# Clock_fanout.net
KiCad netlist of a schematic drawn in Altium Designer
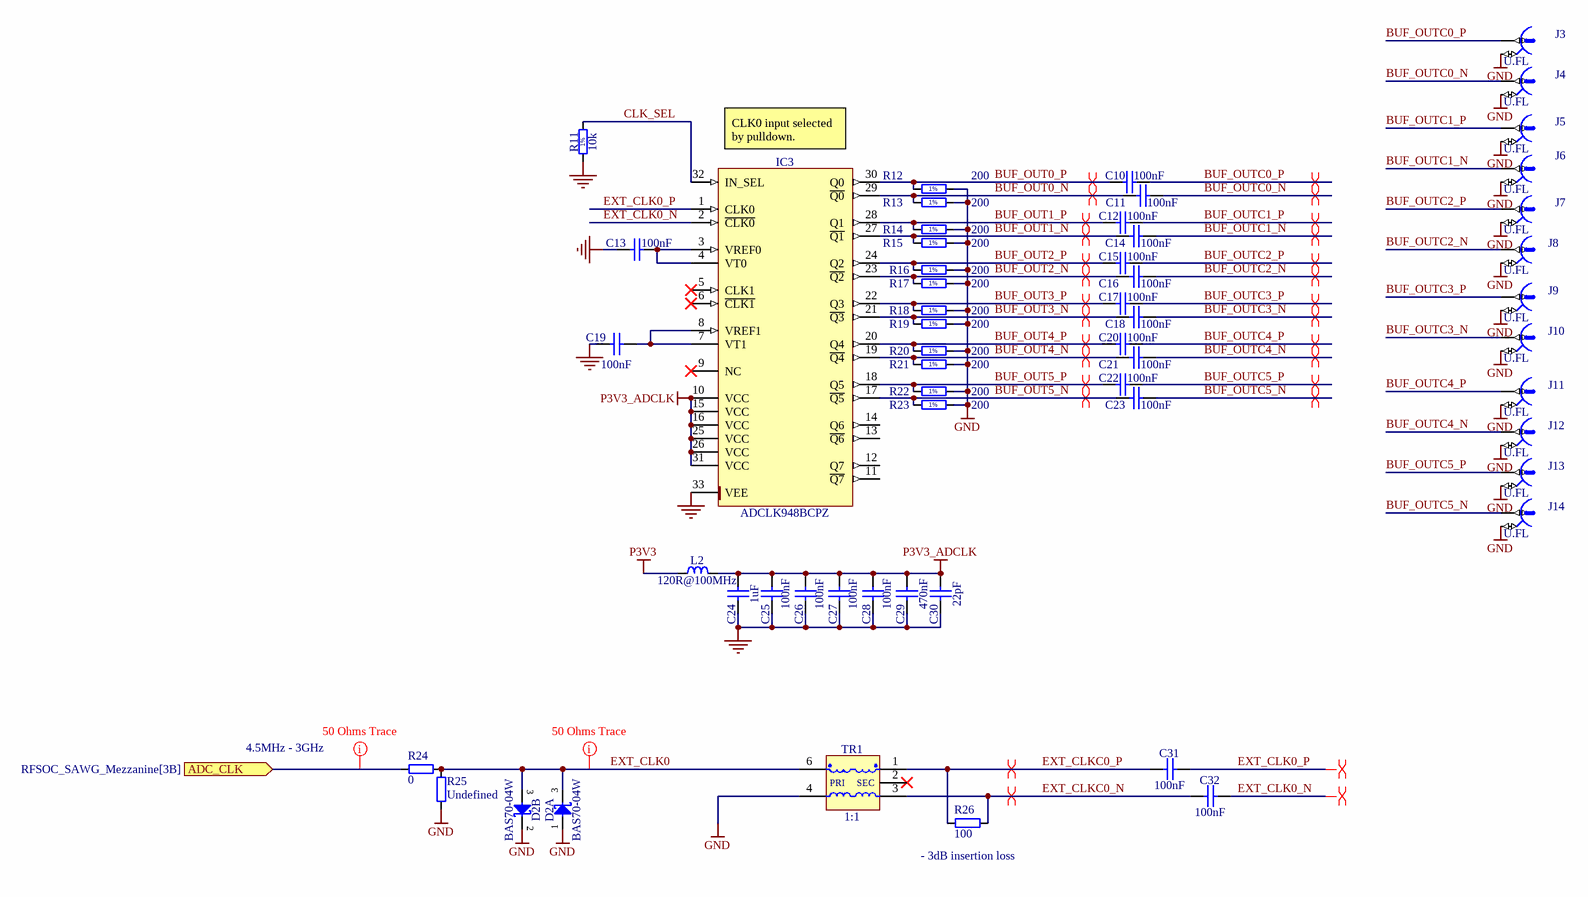
[diagram p0: Clock_fanout.SchDoc]

(export (version "E")
  (design (tool "Eeschema 10.0.6"))
  (components
    (comp (ref "C10")
      (value "100nF")
      (footprint "CAPC0603X33N")
      (description "Non-polarised capacitor")
      (fields
        (field (name "PART NUMBER") "CC0201_100NF_6.3V_10%_X5R")
        (field (name "VOLTAGE") "6.3V")
        (field (name "AUTHOR") "CERN DEM JLC")
      )
      (libsource (lib "Capacitors") (part "Capacitor - non polarized"))
    )
    (comp (ref "C11")
      (value "100nF")
      (footprint "CAPC0603X33N")
      (description "Non-polarised capacitor")
      (fields
        (field (name "PART NUMBER") "CC0201_100NF_6.3V_10%_X5R")
        (field (name "VOLTAGE") "6.3V")
        (field (name "AUTHOR") "CERN DEM JLC")
      )
      (libsource (lib "Capacitors") (part "Capacitor - non polarized"))
    )
    (comp (ref "C12")
      (value "100nF")
      (footprint "CAPC0603X33N")
      (description "Non-polarised capacitor")
      (fields
        (field (name "PART NUMBER") "CC0201_100NF_6.3V_10%_X5R")
        (field (name "VOLTAGE") "6.3V")
        (field (name "AUTHOR") "CERN DEM JLC")
      )
      (libsource (lib "Capacitors") (part "Capacitor - non polarized"))
    )
    (comp (ref "C13")
      (value "100nF")
      (footprint "CAPC0603X33N")
      (description "Non-polarised capacitor")
      (fields
        (field (name "PART NUMBER") "CC0201_100NF_6.3V_10%_X5R")
        (field (name "VOLTAGE") "6.3V")
        (field (name "AUTHOR") "CERN DEM JLC")
      )
      (libsource (lib "Capacitors") (part "Capacitor - non polarized"))
    )
    (comp (ref "C14")
      (value "100nF")
      (footprint "CAPC0603X33N")
      (description "Non-polarised capacitor")
      (fields
        (field (name "PART NUMBER") "CC0201_100NF_6.3V_10%_X5R")
        (field (name "VOLTAGE") "6.3V")
        (field (name "AUTHOR") "CERN DEM JLC")
      )
      (libsource (lib "Capacitors") (part "Capacitor - non polarized"))
    )
    (comp (ref "C15")
      (value "100nF")
      (footprint "CAPC0603X33N")
      (description "Non-polarised capacitor")
      (fields
        (field (name "PART NUMBER") "CC0201_100NF_6.3V_10%_X5R")
        (field (name "VOLTAGE") "6.3V")
        (field (name "AUTHOR") "CERN DEM JLC")
      )
      (libsource (lib "Capacitors") (part "Capacitor - non polarized"))
    )
    (comp (ref "C16")
      (value "100nF")
      (footprint "CAPC0603X33N")
      (description "Non-polarised capacitor")
      (fields
        (field (name "PART NUMBER") "CC0201_100NF_6.3V_10%_X5R")
        (field (name "VOLTAGE") "6.3V")
        (field (name "AUTHOR") "CERN DEM JLC")
      )
      (libsource (lib "Capacitors") (part "Capacitor - non polarized"))
    )
    (comp (ref "C17")
      (value "100nF")
      (footprint "CAPC0603X33N")
      (description "Non-polarised capacitor")
      (fields
        (field (name "PART NUMBER") "CC0201_100NF_6.3V_10%_X5R")
        (field (name "VOLTAGE") "6.3V")
        (field (name "AUTHOR") "CERN DEM JLC")
      )
      (libsource (lib "Capacitors") (part "Capacitor - non polarized"))
    )
    (comp (ref "C18")
      (value "100nF")
      (footprint "CAPC0603X33N")
      (description "Non-polarised capacitor")
      (fields
        (field (name "PART NUMBER") "CC0201_100NF_6.3V_10%_X5R")
        (field (name "VOLTAGE") "6.3V")
        (field (name "AUTHOR") "CERN DEM JLC")
      )
      (libsource (lib "Capacitors") (part "Capacitor - non polarized"))
    )
    (comp (ref "C19")
      (value "100nF")
      (footprint "CAPC0603X33N")
      (description "Non-polarised capacitor")
      (fields
        (field (name "PART NUMBER") "CC0201_100NF_6.3V_10%_X5R")
        (field (name "VOLTAGE") "6.3V")
        (field (name "AUTHOR") "CERN DEM JLC")
      )
      (libsource (lib "Capacitors") (part "Capacitor - non polarized"))
    )
    (comp (ref "C20")
      (value "100nF")
      (footprint "CAPC0603X33N")
      (description "Non-polarised capacitor")
      (fields
        (field (name "PART NUMBER") "CC0201_100NF_6.3V_10%_X5R")
        (field (name "VOLTAGE") "6.3V")
        (field (name "AUTHOR") "CERN DEM JLC")
      )
      (libsource (lib "Capacitors") (part "Capacitor - non polarized"))
    )
    (comp (ref "C21")
      (value "100nF")
      (footprint "CAPC0603X33N")
      (description "Non-polarised capacitor")
      (fields
        (field (name "PART NUMBER") "CC0201_100NF_6.3V_10%_X5R")
        (field (name "VOLTAGE") "6.3V")
        (field (name "AUTHOR") "CERN DEM JLC")
      )
      (libsource (lib "Capacitors") (part "Capacitor - non polarized"))
    )
    (comp (ref "C22")
      (value "100nF")
      (footprint "CAPC0603X33N")
      (description "Non-polarised capacitor")
      (fields
        (field (name "PART NUMBER") "CC0201_100NF_6.3V_10%_X5R")
        (field (name "VOLTAGE") "6.3V")
        (field (name "AUTHOR") "CERN DEM JLC")
      )
      (libsource (lib "Capacitors") (part "Capacitor - non polarized"))
    )
    (comp (ref "C23")
      (value "100nF")
      (footprint "CAPC0603X33N")
      (description "Non-polarised capacitor")
      (fields
        (field (name "PART NUMBER") "CC0201_100NF_6.3V_10%_X5R")
        (field (name "VOLTAGE") "6.3V")
        (field (name "AUTHOR") "CERN DEM JLC")
      )
      (libsource (lib "Capacitors") (part "Capacitor - non polarized"))
    )
    (comp (ref "C24")
      (value "1uF")
      (footprint "CAPC1005X55N")
      (description "Non-polarised capacitor")
      (fields
        (field (name "PART NUMBER") "CC0402_1UF_16V_10%_X5R")
        (field (name "VOLTAGE") "16V")
        (field (name "AUTHOR") "CERN DEM JLC")
      )
      (libsource (lib "Capacitors") (part "Capacitor - non polarized"))
    )
    (comp (ref "C25")
      (value "100nF")
      (footprint "CAPC0603X33N")
      (description "Non-polarised capacitor")
      (fields
        (field (name "PART NUMBER") "CC0201_100NF_6.3V_10%_X5R")
        (field (name "VOLTAGE") "6.3V")
        (field (name "AUTHOR") "CERN DEM JLC")
      )
      (libsource (lib "Capacitors") (part "Capacitor - non polarized"))
    )
    (comp (ref "C26")
      (value "100nF")
      (footprint "CAPC0603X33N")
      (description "Non-polarised capacitor")
      (fields
        (field (name "PART NUMBER") "CC0201_100NF_6.3V_10%_X5R")
        (field (name "VOLTAGE") "6.3V")
        (field (name "AUTHOR") "CERN DEM JLC")
      )
      (libsource (lib "Capacitors") (part "Capacitor - non polarized"))
    )
    (comp (ref "C27")
      (value "100nF")
      (footprint "CAPC0603X33N")
      (description "Non-polarised capacitor")
      (fields
        (field (name "PART NUMBER") "CC0201_100NF_6.3V_10%_X5R")
        (field (name "VOLTAGE") "6.3V")
        (field (name "AUTHOR") "CERN DEM JLC")
      )
      (libsource (lib "Capacitors") (part "Capacitor - non polarized"))
    )
    (comp (ref "C28")
      (value "100nF")
      (footprint "CAPC0603X33N")
      (description "Non-polarised capacitor")
      (fields
        (field (name "PART NUMBER") "CC0201_100NF_6.3V_10%_X5R")
        (field (name "VOLTAGE") "6.3V")
        (field (name "AUTHOR") "CERN DEM JLC")
      )
      (libsource (lib "Capacitors") (part "Capacitor - non polarized"))
    )
    (comp (ref "C29")
      (value "470nF")
      (footprint "CAPC0603X33N")
      (description "Non-polarised capacitor")
      (fields
        (field (name "PART NUMBER") "CC0201_470NF_4V_20%_X5R")
        (field (name "VOLTAGE") "4V")
        (field (name "AUTHOR") "CERN DEM JLC")
      )
      (libsource (lib "Capacitors") (part "Capacitor - non polarized"))
    )
    (comp (ref "C30")
      (value "22pF")
      (footprint "CAPC1005X55N")
      (description "Non-polarised capacitor")
      (fields
        (field (name "PART NUMBER") "CC0402_22PF_50V_5%_C0G")
        (field (name "VOLTAGE") "50V")
        (field (name "AUTHOR") "CERN DEM JLC")
      )
      (libsource (lib "Capacitors") (part "Capacitor - non polarized"))
    )
    (comp (ref "C31")
      (value "100nF")
      (footprint "CAPC0603X33N")
      (description "Non-polarised capacitor")
      (fields
        (field (name "PART NUMBER") "CC0201_100NF_6.3V_10%_X5R")
        (field (name "VOLTAGE") "6.3V")
        (field (name "AUTHOR") "CERN DEM JLC")
      )
      (libsource (lib "Capacitors") (part "Capacitor - non polarized"))
    )
    (comp (ref "C32")
      (value "100nF")
      (footprint "CAPC0603X33N")
      (description "Non-polarised capacitor")
      (fields
        (field (name "PART NUMBER") "CC0201_100NF_6.3V_10%_X5R")
        (field (name "VOLTAGE") "6.3V")
        (field (name "AUTHOR") "CERN DEM JLC")
      )
      (libsource (lib "Capacitors") (part "Capacitor - non polarized"))
    )
    (comp (ref "D2")
      (value "BAS70-04W")
      (footprint "SOT65P210X110-3N")
      (description "Serial Schottky Diode")
      (fields
        (field (name "VOLTAGE") "70V")
        (field (name "POWER") "70mA")
        (field (name "AUTHOR") "CERN DEM JLC")
      )
      (libsource (lib "ICs And Semiconductors") (part "Diode Schottky x2 A1C3_A3C2"))
    )
    (comp (ref "IC3")
      (value "ADCLK948BCPZ")
      (footprint "QFN50P500X500X80-33N-S285")
      (description "Two Selectable Inputs, 8 LVPECL Outputs, SiGe Clock Fanout Buffer")
      (fields (field (name "MANUFACTURER") "ANALOG DEVICES") (field (name "AUTHOR") "CERN DEM MR"))
      (libsource (lib "ICs And Semiconductors") (part "ADCLK948"))
    )
    (comp (ref "J3")
      (value "U.FL")
      (footprint "HIROSE_U.FL-R-SMT-1(10)")
      (fields
        (field (name "PART NUMBER") "HIROSE_U.FL-R-SMT-1(10)")
        (field (name "MANUFACTURER") "HIROSE (HRS)")
        (field (name "MANUFACTURER PART NUMBER") "U.FL-R-SMT-1(10)")
        (field (name "AUTHOR") "CERN DEM JLC")
      )
      (libsource (lib "Connectors") (part "Coax_1Male_1Shield"))
    )
    (comp (ref "J4")
      (value "U.FL")
      (footprint "HIROSE_U.FL-R-SMT-1(10)")
      (fields
        (field (name "PART NUMBER") "HIROSE_U.FL-R-SMT-1(10)")
        (field (name "MANUFACTURER") "HIROSE (HRS)")
        (field (name "MANUFACTURER PART NUMBER") "U.FL-R-SMT-1(10)")
        (field (name "AUTHOR") "CERN DEM JLC")
      )
      (libsource (lib "Connectors") (part "Coax_1Male_1Shield"))
    )
    (comp (ref "J5")
      (value "U.FL")
      (footprint "HIROSE_U.FL-R-SMT-1(10)")
      (fields
        (field (name "PART NUMBER") "HIROSE_U.FL-R-SMT-1(10)")
        (field (name "MANUFACTURER") "HIROSE (HRS)")
        (field (name "MANUFACTURER PART NUMBER") "U.FL-R-SMT-1(10)")
        (field (name "AUTHOR") "CERN DEM JLC")
      )
      (libsource (lib "Connectors") (part "Coax_1Male_1Shield"))
    )
    (comp (ref "J6")
      (value "U.FL")
      (footprint "HIROSE_U.FL-R-SMT-1(10)")
      (fields
        (field (name "PART NUMBER") "HIROSE_U.FL-R-SMT-1(10)")
        (field (name "MANUFACTURER") "HIROSE (HRS)")
        (field (name "MANUFACTURER PART NUMBER") "U.FL-R-SMT-1(10)")
        (field (name "AUTHOR") "CERN DEM JLC")
      )
      (libsource (lib "Connectors") (part "Coax_1Male_1Shield"))
    )
    (comp (ref "J7")
      (value "U.FL")
      (footprint "HIROSE_U.FL-R-SMT-1(10)")
      (fields
        (field (name "PART NUMBER") "HIROSE_U.FL-R-SMT-1(10)")
        (field (name "MANUFACTURER") "HIROSE (HRS)")
        (field (name "MANUFACTURER PART NUMBER") "U.FL-R-SMT-1(10)")
        (field (name "AUTHOR") "CERN DEM JLC")
      )
      (libsource (lib "Connectors") (part "Coax_1Male_1Shield"))
    )
    (comp (ref "J8")
      (value "U.FL")
      (footprint "HIROSE_U.FL-R-SMT-1(10)")
      (fields
        (field (name "PART NUMBER") "HIROSE_U.FL-R-SMT-1(10)")
        (field (name "MANUFACTURER") "HIROSE (HRS)")
        (field (name "MANUFACTURER PART NUMBER") "U.FL-R-SMT-1(10)")
        (field (name "AUTHOR") "CERN DEM JLC")
      )
      (libsource (lib "Connectors") (part "Coax_1Male_1Shield"))
    )
    (comp (ref "J9")
      (value "U.FL")
      (footprint "HIROSE_U.FL-R-SMT-1(10)")
      (fields
        (field (name "PART NUMBER") "HIROSE_U.FL-R-SMT-1(10)")
        (field (name "MANUFACTURER") "HIROSE (HRS)")
        (field (name "MANUFACTURER PART NUMBER") "U.FL-R-SMT-1(10)")
        (field (name "AUTHOR") "CERN DEM JLC")
      )
      (libsource (lib "Connectors") (part "Coax_1Male_1Shield"))
    )
    (comp (ref "J10")
      (value "U.FL")
      (footprint "HIROSE_U.FL-R-SMT-1(10)")
      (fields
        (field (name "PART NUMBER") "HIROSE_U.FL-R-SMT-1(10)")
        (field (name "MANUFACTURER") "HIROSE (HRS)")
        (field (name "MANUFACTURER PART NUMBER") "U.FL-R-SMT-1(10)")
        (field (name "AUTHOR") "CERN DEM JLC")
      )
      (libsource (lib "Connectors") (part "Coax_1Male_1Shield"))
    )
    (comp (ref "J11")
      (value "U.FL")
      (footprint "HIROSE_U.FL-R-SMT-1(10)")
      (fields
        (field (name "PART NUMBER") "HIROSE_U.FL-R-SMT-1(10)")
        (field (name "MANUFACTURER") "HIROSE (HRS)")
        (field (name "MANUFACTURER PART NUMBER") "U.FL-R-SMT-1(10)")
        (field (name "AUTHOR") "CERN DEM JLC")
      )
      (libsource (lib "Connectors") (part "Coax_1Male_1Shield"))
    )
    (comp (ref "J12")
      (value "U.FL")
      (footprint "HIROSE_U.FL-R-SMT-1(10)")
      (fields
        (field (name "PART NUMBER") "HIROSE_U.FL-R-SMT-1(10)")
        (field (name "MANUFACTURER") "HIROSE (HRS)")
        (field (name "MANUFACTURER PART NUMBER") "U.FL-R-SMT-1(10)")
        (field (name "AUTHOR") "CERN DEM JLC")
      )
      (libsource (lib "Connectors") (part "Coax_1Male_1Shield"))
    )
    (comp (ref "J13")
      (value "U.FL")
      (footprint "HIROSE_U.FL-R-SMT-1(10)")
      (fields
        (field (name "PART NUMBER") "HIROSE_U.FL-R-SMT-1(10)")
        (field (name "MANUFACTURER") "HIROSE (HRS)")
        (field (name "MANUFACTURER PART NUMBER") "U.FL-R-SMT-1(10)")
        (field (name "AUTHOR") "CERN DEM JLC")
      )
      (libsource (lib "Connectors") (part "Coax_1Male_1Shield"))
    )
    (comp (ref "J14")
      (value "U.FL")
      (footprint "HIROSE_U.FL-R-SMT-1(10)")
      (fields
        (field (name "PART NUMBER") "HIROSE_U.FL-R-SMT-1(10)")
        (field (name "MANUFACTURER") "HIROSE (HRS)")
        (field (name "MANUFACTURER PART NUMBER") "U.FL-R-SMT-1(10)")
        (field (name "AUTHOR") "CERN DEM JLC")
      )
      (libsource (lib "Connectors") (part "Coax_1Male_1Shield"))
    )
    (comp (ref "L2")
      (value "120R@100MHz")
      (footprint "INDC1608X65N")
      (description "Inductor")
      (fields
        (field (name "PART NUMBER") "IND0603_MURATA_BLM18SG121TN1D")
        (field (name "POWER") "3A")
        (field (name "AUTHOR") "CERN DEM JLC")
      )
      (libsource (lib "Inductors & Transformers") (part "Inductor"))
    )
    (comp (ref "R11")
      (value "10k")
      (footprint "RESC1005X40N")
      (description "Resistor - 1%")
      (fields
        (field (name "PART NUMBER") "R0402_10K_1%_0.0625W_100PPM")
        (field (name "POWER") "0.0625W")
        (field (name "AUTHOR") "CERN DEM JLC")
      )
      (libsource (lib "Resistors") (part "Resistor - 1%"))
    )
    (comp (ref "R12")
      (value "200")
      (footprint "RESC1005X40N")
      (description "Resistor - 1%")
      (fields
        (field (name "PART NUMBER") "R0402_200R_1%_0.0625W_100PPM")
        (field (name "POWER") "0.0625W")
        (field (name "AUTHOR") "CERN DEM JLC")
      )
      (libsource (lib "Resistors") (part "Resistor - 1%"))
    )
    (comp (ref "R13")
      (value "200")
      (footprint "RESC1005X40N")
      (description "Resistor - 1%")
      (fields
        (field (name "PART NUMBER") "R0402_200R_1%_0.0625W_100PPM")
        (field (name "POWER") "0.0625W")
        (field (name "AUTHOR") "CERN DEM JLC")
      )
      (libsource (lib "Resistors") (part "Resistor - 1%"))
    )
    (comp (ref "R14")
      (value "200")
      (footprint "RESC1005X40N")
      (description "Resistor - 1%")
      (fields
        (field (name "PART NUMBER") "R0402_200R_1%_0.0625W_100PPM")
        (field (name "POWER") "0.0625W")
        (field (name "AUTHOR") "CERN DEM JLC")
      )
      (libsource (lib "Resistors") (part "Resistor - 1%"))
    )
    (comp (ref "R15")
      (value "200")
      (footprint "RESC1005X40N")
      (description "Resistor - 1%")
      (fields
        (field (name "PART NUMBER") "R0402_200R_1%_0.0625W_100PPM")
        (field (name "POWER") "0.0625W")
        (field (name "AUTHOR") "CERN DEM JLC")
      )
      (libsource (lib "Resistors") (part "Resistor - 1%"))
    )
    (comp (ref "R16")
      (value "200")
      (footprint "RESC1005X40N")
      (description "Resistor - 1%")
      (fields
        (field (name "PART NUMBER") "R0402_200R_1%_0.0625W_100PPM")
        (field (name "POWER") "0.0625W")
        (field (name "AUTHOR") "CERN DEM JLC")
      )
      (libsource (lib "Resistors") (part "Resistor - 1%"))
    )
    (comp (ref "R17")
      (value "200")
      (footprint "RESC1005X40N")
      (description "Resistor - 1%")
      (fields
        (field (name "PART NUMBER") "R0402_200R_1%_0.0625W_100PPM")
        (field (name "POWER") "0.0625W")
        (field (name "AUTHOR") "CERN DEM JLC")
      )
      (libsource (lib "Resistors") (part "Resistor - 1%"))
    )
    (comp (ref "R18")
      (value "200")
      (footprint "RESC1005X40N")
      (description "Resistor - 1%")
      (fields
        (field (name "PART NUMBER") "R0402_200R_1%_0.0625W_100PPM")
        (field (name "POWER") "0.0625W")
        (field (name "AUTHOR") "CERN DEM JLC")
      )
      (libsource (lib "Resistors") (part "Resistor - 1%"))
    )
    (comp (ref "R19")
      (value "200")
      (footprint "RESC1005X40N")
      (description "Resistor - 1%")
      (fields
        (field (name "PART NUMBER") "R0402_200R_1%_0.0625W_100PPM")
        (field (name "POWER") "0.0625W")
        (field (name "AUTHOR") "CERN DEM JLC")
      )
      (libsource (lib "Resistors") (part "Resistor - 1%"))
    )
    (comp (ref "R20")
      (value "200")
      (footprint "RESC1005X40N")
      (description "Resistor - 1%")
      (fields
        (field (name "PART NUMBER") "R0402_200R_1%_0.0625W_100PPM")
        (field (name "POWER") "0.0625W")
        (field (name "AUTHOR") "CERN DEM JLC")
      )
      (libsource (lib "Resistors") (part "Resistor - 1%"))
    )
    (comp (ref "R21")
      (value "200")
      (footprint "RESC1005X40N")
      (description "Resistor - 1%")
      (fields
        (field (name "PART NUMBER") "R0402_200R_1%_0.0625W_100PPM")
        (field (name "POWER") "0.0625W")
        (field (name "AUTHOR") "CERN DEM JLC")
      )
      (libsource (lib "Resistors") (part "Resistor - 1%"))
    )
    (comp (ref "R22")
      (value "200")
      (footprint "RESC1005X40N")
      (description "Resistor - 1%")
      (fields
        (field (name "PART NUMBER") "R0402_200R_1%_0.0625W_100PPM")
        (field (name "POWER") "0.0625W")
        (field (name "AUTHOR") "CERN DEM JLC")
      )
      (libsource (lib "Resistors") (part "Resistor - 1%"))
    )
    (comp (ref "R23")
      (value "200")
      (footprint "RESC1005X40N")
      (description "Resistor - 1%")
      (fields
        (field (name "PART NUMBER") "R0402_200R_1%_0.0625W_100PPM")
        (field (name "POWER") "0.0625W")
        (field (name "AUTHOR") "CERN DEM JLC")
      )
      (libsource (lib "Resistors") (part "Resistor - 1%"))
    )
    (comp (ref "R24")
      (value "0")
      (footprint "RESC1005X40N")
      (description "Resistor")
      (fields
        (field (name "PART NUMBER") "R0402_0R_JUMPER")
        (field (name "MANUFACTURER") "GENERIC")
        (field (name "AUTHOR") "CERN DEM JLC")
      )
      (libsource (lib "Resistors") (part "Resistor"))
    )
    (comp (ref "R25")
      (value "Undefined")
      (footprint "RESC1005X40N")
      (description "Resistor")
      (fields (field (name "PART NUMBER") "R0402_NO-VALUE") (field (name "AUTHOR") "CERN DEM JLC"))
      (libsource (lib "Resistors") (part "Resistor"))
    )
    (comp (ref "R26")
      (value "100")
      (footprint "RESC1005X35N")
      (description "Resistor - 0.1%")
      (fields
        (field (name "TOLERANCE") "±0.1%")
        (field (name "PART NUMBER") "R0402_100R_0.1%_0.063W_25PPM")
        (field (name "AUTHOR") "CERN DEM JMW")
      )
      (libsource (lib "Resistors") (part "Resistor - 0.1%"))
    )
    (comp (ref "TR1")
      (value "1:1")
      (footprint "XFMR_MINI-CIRCUITS_AT224")
      (description "50 Ohms 4.5 To 3000MHz RF Transformers")
      (fields
        (field (name "PART NUMBER") "XFMR_MINI-CIRCUITS_TC1-1-13M+")
        (field (name "MANUFACTURER") "MINI-CIRCUITS")
        (field (name "AUTHOR") "CERN DEM JLC")
      )
      (libsource (lib "Inductors & Transformers") (part "XFMR_MINI-CIRCUITS_TC1-1-13M+"))
    )
  )
  (nets
    (net (code "1") (name "/ADC_CLK") (class "Default")
      (node (ref "R24") (pin "1") (pinfunction "1_1") (pintype "passive"))
    )
    (net (code "2") (name "/BUF_OUT0_N") (class "Default")
      (node (ref "C11") (pin "1") (pinfunction "1_1") (pintype "passive"))
      (node (ref "IC3") (pin "29") (pinfunction "~{Q0}_29") (pintype "output"))
      (node (ref "R13") (pin "1") (pinfunction "1_1") (pintype "passive"))
    )
    (net (code "3") (name "/BUF_OUT0_P") (class "Default")
      (node (ref "C10") (pin "1") (pinfunction "1_1") (pintype "passive"))
      (node (ref "IC3") (pin "30") (pinfunction "Q0_30") (pintype "output"))
      (node (ref "R12") (pin "1") (pinfunction "1_1") (pintype "passive"))
    )
    (net (code "4") (name "/BUF_OUT1_N") (class "Default")
      (node (ref "C14") (pin "1") (pinfunction "1_1") (pintype "passive"))
      (node (ref "IC3") (pin "27") (pinfunction "~{Q1}_27") (pintype "output"))
      (node (ref "R15") (pin "1") (pinfunction "1_1") (pintype "passive"))
    )
    (net (code "5") (name "/BUF_OUT1_P") (class "Default")
      (node (ref "C12") (pin "1") (pinfunction "1_1") (pintype "passive"))
      (node (ref "IC3") (pin "28") (pinfunction "Q1_28") (pintype "output"))
      (node (ref "R14") (pin "1") (pinfunction "1_1") (pintype "passive"))
    )
    (net (code "6") (name "/BUF_OUT2_N") (class "Default")
      (node (ref "C16") (pin "1") (pinfunction "1_1") (pintype "passive"))
      (node (ref "IC3") (pin "23") (pinfunction "~{Q2}_23") (pintype "output"))
      (node (ref "R17") (pin "1") (pinfunction "1_1") (pintype "passive"))
    )
    (net (code "7") (name "/BUF_OUT2_P") (class "Default")
      (node (ref "C15") (pin "1") (pinfunction "1_1") (pintype "passive"))
      (node (ref "IC3") (pin "24") (pinfunction "Q2_24") (pintype "output"))
      (node (ref "R16") (pin "1") (pinfunction "1_1") (pintype "passive"))
    )
    (net (code "8") (name "/BUF_OUT3_N") (class "Default")
      (node (ref "C18") (pin "1") (pinfunction "1_1") (pintype "passive"))
      (node (ref "IC3") (pin "21") (pinfunction "~{Q3}_21") (pintype "output"))
      (node (ref "R19") (pin "1") (pinfunction "1_1") (pintype "passive"))
    )
    (net (code "9") (name "/BUF_OUT3_P") (class "Default")
      (node (ref "C17") (pin "1") (pinfunction "1_1") (pintype "passive"))
      (node (ref "IC3") (pin "22") (pinfunction "Q3_22") (pintype "output"))
      (node (ref "R18") (pin "1") (pinfunction "1_1") (pintype "passive"))
    )
    (net (code "10") (name "/BUF_OUT4_N") (class "Default")
      (node (ref "C21") (pin "1") (pinfunction "1_1") (pintype "passive"))
      (node (ref "IC3") (pin "19") (pinfunction "~{Q4}_19") (pintype "output"))
      (node (ref "R21") (pin "1") (pinfunction "1_1") (pintype "passive"))
    )
    (net (code "11") (name "/BUF_OUT4_P") (class "Default")
      (node (ref "C20") (pin "1") (pinfunction "1_1") (pintype "passive"))
      (node (ref "IC3") (pin "20") (pinfunction "Q4_20") (pintype "output"))
      (node (ref "R20") (pin "1") (pinfunction "1_1") (pintype "passive"))
    )
    (net (code "12") (name "/BUF_OUT5_N") (class "Default")
      (node (ref "C23") (pin "1") (pinfunction "1_1") (pintype "passive"))
      (node (ref "IC3") (pin "17") (pinfunction "~{Q5}_17") (pintype "output"))
      (node (ref "R23") (pin "1") (pinfunction "1_1") (pintype "passive"))
    )
    (net (code "13") (name "/BUF_OUT5_P") (class "Default")
      (node (ref "C22") (pin "1") (pinfunction "1_1") (pintype "passive"))
      (node (ref "IC3") (pin "18") (pinfunction "Q5_18") (pintype "output"))
      (node (ref "R22") (pin "1") (pinfunction "1_1") (pintype "passive"))
    )
    (net (code "14") (name "/BUF_OUTC0_N") (class "Default")
      (node (ref "C11") (pin "2") (pinfunction "2_2") (pintype "passive"))
      (node (ref "J4") (pin "1") (pinfunction "1_1") (pintype "bidirectional"))
    )
    (net (code "15") (name "/BUF_OUTC0_P") (class "Default")
      (node (ref "C10") (pin "2") (pinfunction "2_2") (pintype "passive"))
      (node (ref "J3") (pin "1") (pinfunction "1_1") (pintype "bidirectional"))
    )
    (net (code "16") (name "/BUF_OUTC1_N") (class "Default")
      (node (ref "C14") (pin "2") (pinfunction "2_2") (pintype "passive"))
      (node (ref "J6") (pin "1") (pinfunction "1_1") (pintype "bidirectional"))
    )
    (net (code "17") (name "/BUF_OUTC1_P") (class "Default")
      (node (ref "C12") (pin "2") (pinfunction "2_2") (pintype "passive"))
      (node (ref "J5") (pin "1") (pinfunction "1_1") (pintype "bidirectional"))
    )
    (net (code "18") (name "/BUF_OUTC2_N") (class "Default")
      (node (ref "C16") (pin "2") (pinfunction "2_2") (pintype "passive"))
      (node (ref "J8") (pin "1") (pinfunction "1_1") (pintype "bidirectional"))
    )
    (net (code "19") (name "/BUF_OUTC2_P") (class "Default")
      (node (ref "C15") (pin "2") (pinfunction "2_2") (pintype "passive"))
      (node (ref "J7") (pin "1") (pinfunction "1_1") (pintype "bidirectional"))
    )
    (net (code "20") (name "/BUF_OUTC3_N") (class "Default")
      (node (ref "C18") (pin "2") (pinfunction "2_2") (pintype "passive"))
      (node (ref "J10") (pin "1") (pinfunction "1_1") (pintype "bidirectional"))
    )
    (net (code "21") (name "/BUF_OUTC3_P") (class "Default")
      (node (ref "C17") (pin "2") (pinfunction "2_2") (pintype "passive"))
      (node (ref "J9") (pin "1") (pinfunction "1_1") (pintype "bidirectional"))
    )
    (net (code "22") (name "/BUF_OUTC4_N") (class "Default")
      (node (ref "C21") (pin "2") (pinfunction "2_2") (pintype "passive"))
      (node (ref "J12") (pin "1") (pinfunction "1_1") (pintype "bidirectional"))
    )
    (net (code "23") (name "/BUF_OUTC4_P") (class "Default")
      (node (ref "C20") (pin "2") (pinfunction "2_2") (pintype "passive"))
      (node (ref "J11") (pin "1") (pinfunction "1_1") (pintype "bidirectional"))
    )
    (net (code "24") (name "/BUF_OUTC5_N") (class "Default")
      (node (ref "C23") (pin "2") (pinfunction "2_2") (pintype "passive"))
      (node (ref "J14") (pin "1") (pinfunction "1_1") (pintype "bidirectional"))
    )
    (net (code "25") (name "/BUF_OUTC5_P") (class "Default")
      (node (ref "C22") (pin "2") (pinfunction "2_2") (pintype "passive"))
      (node (ref "J13") (pin "1") (pinfunction "1_1") (pintype "bidirectional"))
    )
    (net (code "26") (name "/CLK_SEL") (class "Default")
      (node (ref "IC3") (pin "32") (pinfunction "IN_SEL_32") (pintype "input"))
      (node (ref "R11") (pin "2") (pinfunction "2_2") (pintype "passive"))
    )
    (net (code "27") (name "/EXT_CLK0") (class "Default")
      (node (ref "D2") (pin "3") (pinfunction "COMAC_3") (pintype "passive"))
      (node (ref "R24") (pin "2") (pinfunction "2_2") (pintype "passive"))
      (node (ref "R25") (pin "1") (pinfunction "1_1") (pintype "passive"))
      (node (ref "TR1") (pin "6") (pinfunction "PDOT_6") (pintype "passive"))
    )
    (net (code "28") (name "/EXT_CLK0_N") (class "Default")
      (node (ref "C32") (pin "2") (pinfunction "2_2") (pintype "passive"))
      (node (ref "IC3") (pin "2") (pinfunction "~{CLK0}_2") (pintype "input"))
    )
    (net (code "29") (name "/EXT_CLK0_P") (class "Default")
      (node (ref "C31") (pin "2") (pinfunction "2_2") (pintype "passive"))
      (node (ref "IC3") (pin "1") (pinfunction "CLK0_1") (pintype "input"))
    )
    (net (code "30") (name "/EXT_CLKC0_N") (class "Default")
      (node (ref "C32") (pin "1") (pinfunction "1_1") (pintype "passive"))
      (node (ref "R26") (pin "2") (pinfunction "2_2") (pintype "passive"))
      (node (ref "TR1") (pin "3") (pinfunction "S_3") (pintype "passive"))
    )
    (net (code "31") (name "/EXT_CLKC0_P") (class "Default")
      (node (ref "C31") (pin "1") (pinfunction "1_1") (pintype "passive"))
      (node (ref "R26") (pin "1") (pinfunction "1_1") (pintype "passive"))
      (node (ref "TR1") (pin "1") (pinfunction "SDOT_1") (pintype "passive"))
    )
    (net (code "32") (name "GND") (class "Default")
      (node (ref "C13") (pin "1") (pinfunction "1_1") (pintype "passive"))
      (node (ref "C19") (pin "1") (pinfunction "1_1") (pintype "passive"))
      (node (ref "C24") (pin "1") (pinfunction "1_1") (pintype "passive"))
      (node (ref "C25") (pin "1") (pinfunction "1_1") (pintype "passive"))
      (node (ref "C26") (pin "1") (pinfunction "1_1") (pintype "passive"))
      (node (ref "C27") (pin "1") (pinfunction "1_1") (pintype "passive"))
      (node (ref "C28") (pin "1") (pinfunction "1_1") (pintype "passive"))
      (node (ref "C29") (pin "1") (pinfunction "1_1") (pintype "passive"))
      (node (ref "C30") (pin "1") (pinfunction "1_1") (pintype "passive"))
      (node (ref "D2") (pin "1") (pinfunction "A_1") (pintype "passive"))
      (node (ref "D2") (pin "2") (pinfunction "C_2") (pintype "passive"))
      (node (ref "IC3") (pin "33") (pinfunction "VEE_33") (pintype "power_in"))
      (node (ref "J10") (pin "2") (pinfunction "2_2") (pintype "bidirectional"))
      (node (ref "J11") (pin "2") (pinfunction "2_2") (pintype "bidirectional"))
      (node (ref "J12") (pin "2") (pinfunction "2_2") (pintype "bidirectional"))
      (node (ref "J13") (pin "2") (pinfunction "2_2") (pintype "bidirectional"))
      (node (ref "J14") (pin "2") (pinfunction "2_2") (pintype "bidirectional"))
      (node (ref "J3") (pin "2") (pinfunction "2_2") (pintype "bidirectional"))
      (node (ref "J4") (pin "2") (pinfunction "2_2") (pintype "bidirectional"))
      (node (ref "J5") (pin "2") (pinfunction "2_2") (pintype "bidirectional"))
      (node (ref "J6") (pin "2") (pinfunction "2_2") (pintype "bidirectional"))
      (node (ref "J7") (pin "2") (pinfunction "2_2") (pintype "bidirectional"))
      (node (ref "J8") (pin "2") (pinfunction "2_2") (pintype "bidirectional"))
      (node (ref "J9") (pin "2") (pinfunction "2_2") (pintype "bidirectional"))
      (node (ref "R11") (pin "1") (pinfunction "1_1") (pintype "passive"))
      (node (ref "R12") (pin "2") (pinfunction "2_2") (pintype "passive"))
      (node (ref "R13") (pin "2") (pinfunction "2_2") (pintype "passive"))
      (node (ref "R14") (pin "2") (pinfunction "2_2") (pintype "passive"))
      (node (ref "R15") (pin "2") (pinfunction "2_2") (pintype "passive"))
      (node (ref "R16") (pin "2") (pinfunction "2_2") (pintype "passive"))
      (node (ref "R17") (pin "2") (pinfunction "2_2") (pintype "passive"))
      (node (ref "R18") (pin "2") (pinfunction "2_2") (pintype "passive"))
      (node (ref "R19") (pin "2") (pinfunction "2_2") (pintype "passive"))
      (node (ref "R20") (pin "2") (pinfunction "2_2") (pintype "passive"))
      (node (ref "R21") (pin "2") (pinfunction "2_2") (pintype "passive"))
      (node (ref "R22") (pin "2") (pinfunction "2_2") (pintype "passive"))
      (node (ref "R23") (pin "2") (pinfunction "2_2") (pintype "passive"))
      (node (ref "R25") (pin "2") (pinfunction "2_2") (pintype "passive"))
      (node (ref "TR1") (pin "4") (pinfunction "P_4") (pintype "passive"))
    )
    (net (code "33") (name "Net-(IC3-VREF0)") (class "Default")
      (node (ref "C13") (pin "2") (pinfunction "2_2") (pintype "passive"))
      (node (ref "IC3") (pin "3") (pinfunction "VREF0_3") (pintype "input"))
      (node (ref "IC3") (pin "4") (pinfunction "VT0_4") (pintype "passive"))
    )
    (net (code "34") (name "Net-(IC3-VREF1)") (class "Default")
      (node (ref "C19") (pin "2") (pinfunction "2_2") (pintype "passive"))
      (node (ref "IC3") (pin "7") (pinfunction "VT1_7") (pintype "passive"))
      (node (ref "IC3") (pin "8") (pinfunction "VREF1_8") (pintype "input"))
    )
    (net (code "35") (name "P3V3") (class "Default")
      (node (ref "L2") (pin "2") (pinfunction "2_2") (pintype "passive"))
    )
    (net (code "36") (name "P3V3_ADCLK") (class "Default")
      (node (ref "C24") (pin "2") (pinfunction "2_2") (pintype "passive"))
      (node (ref "C25") (pin "2") (pinfunction "2_2") (pintype "passive"))
      (node (ref "C26") (pin "2") (pinfunction "2_2") (pintype "passive"))
      (node (ref "C27") (pin "2") (pinfunction "2_2") (pintype "passive"))
      (node (ref "C28") (pin "2") (pinfunction "2_2") (pintype "passive"))
      (node (ref "C29") (pin "2") (pinfunction "2_2") (pintype "passive"))
      (node (ref "C30") (pin "2") (pinfunction "2_2") (pintype "passive"))
      (node (ref "IC3") (pin "10") (pinfunction "VCC_10") (pintype "power_in"))
      (node (ref "IC3") (pin "15") (pinfunction "VCC_15") (pintype "power_in"))
      (node (ref "IC3") (pin "16") (pinfunction "VCC_16") (pintype "power_in"))
      (node (ref "IC3") (pin "25") (pinfunction "VCC_25") (pintype "power_in"))
      (node (ref "IC3") (pin "26") (pinfunction "VCC_26") (pintype "power_in"))
      (node (ref "IC3") (pin "31") (pinfunction "VCC_31") (pintype "power_in"))
      (node (ref "L2") (pin "1") (pinfunction "1_1") (pintype "passive"))
    )
    (net (code "37") (name "unconnected-(IC3-CLK1-Pad5)") (class "Default")
      (node (ref "IC3") (pin "5") (pinfunction "CLK1_5") (pintype "input+no_connect"))
    )
    (net (code "38") (name "unconnected-(IC3-NC-Pad9)") (class "Default")
      (node (ref "IC3") (pin "9") (pinfunction "NC_9") (pintype "passive+no_connect"))
    )
    (net (code "39") (name "unconnected-(IC3-Q6-Pad14)") (class "Default")
      (node (ref "IC3") (pin "14") (pinfunction "Q6_14") (pintype "output"))
    )
    (net (code "40") (name "unconnected-(IC3-Q7-Pad12)") (class "Default")
      (node (ref "IC3") (pin "12") (pinfunction "Q7_12") (pintype "output"))
    )
    (net (code "41") (name "unconnected-(IC3-~{CLK1}-Pad6)") (class "Default")
      (node (ref "IC3") (pin "6") (pinfunction "~{CLK1}_6") (pintype "input+no_connect"))
    )
    (net (code "42") (name "unconnected-(IC3-~{Q6}-Pad13)") (class "Default")
      (node (ref "IC3") (pin "13") (pinfunction "~{Q6}_13") (pintype "output"))
    )
    (net (code "43") (name "unconnected-(IC3-~{Q7}-Pad11)") (class "Default")
      (node (ref "IC3") (pin "11") (pinfunction "~{Q7}_11") (pintype "output"))
    )
    (net (code "44") (name "unconnected-(TR1-NC-Pad2)") (class "Default")
      (node (ref "TR1") (pin "2") (pinfunction "NC_2") (pintype "passive+no_connect"))
    )
  )
)
